# working.net
KiCad netlist of a schematic drawn in EAGLE
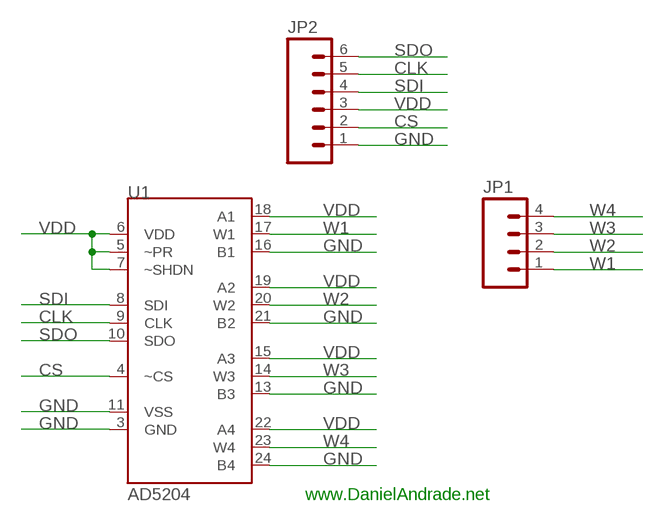
[diagram p0: schematic, sheet 1]

(export (version "E")
  (design (tool "Eeschema 10.0.6"))
  (components
    (comp (ref "JP1")
      (value "M04PTH")
      (footprint "eagle-import:1X04")
      (libsource (lib "eagle-import") (part "M04PTH"))
    )
    (comp (ref "JP2")
      (value "M06SIP")
      (footprint "eagle-import:1X06")
      (libsource (lib "eagle-import") (part "M06SIP"))
    )
    (comp (ref "U1")
      (value "AD5204")
      (footprint "eagle-import:SO24W")
      (libsource (lib "eagle-import") (part "AD5204"))
    )
  )
  (nets
    (net (code "1") (name "/CLK") (class "Default")
      (node (ref "JP2") (pin "5") (pinfunction "5_5") (pintype "passive"))
      (node (ref "U1") (pin "9") (pinfunction "CLK_9") (pintype "bidirectional"))
    )
    (net (code "2") (name "/CS") (class "Default")
      (node (ref "JP2") (pin "2") (pinfunction "2_2") (pintype "passive"))
      (node (ref "U1") (pin "4") (pinfunction "~{CS}_4") (pintype "bidirectional"))
    )
    (net (code "3") (name "/GND") (class "Default")
      (node (ref "JP2") (pin "1") (pinfunction "1_1") (pintype "passive"))
      (node (ref "U1") (pin "11") (pinfunction "VSS_11") (pintype "bidirectional"))
      (node (ref "U1") (pin "13") (pinfunction "B3_13") (pintype "bidirectional"))
      (node (ref "U1") (pin "16") (pinfunction "B1_16") (pintype "bidirectional"))
      (node (ref "U1") (pin "21") (pinfunction "B2_21") (pintype "bidirectional"))
      (node (ref "U1") (pin "24") (pinfunction "B4_24") (pintype "bidirectional"))
      (node (ref "U1") (pin "3") (pinfunction "GND_3") (pintype "bidirectional"))
    )
    (net (code "4") (name "/SDI") (class "Default")
      (node (ref "JP2") (pin "4") (pinfunction "4_4") (pintype "passive"))
      (node (ref "U1") (pin "8") (pinfunction "SDI_8") (pintype "bidirectional"))
    )
    (net (code "5") (name "/SDO") (class "Default")
      (node (ref "JP2") (pin "6") (pinfunction "6_6") (pintype "passive"))
      (node (ref "U1") (pin "10") (pinfunction "SDO_10") (pintype "bidirectional"))
    )
    (net (code "6") (name "/VDD") (class "Default")
      (node (ref "JP2") (pin "3") (pinfunction "3_3") (pintype "passive"))
      (node (ref "U1") (pin "15") (pinfunction "A3_15") (pintype "bidirectional"))
      (node (ref "U1") (pin "18") (pinfunction "A1_18") (pintype "bidirectional"))
      (node (ref "U1") (pin "19") (pinfunction "A2_19") (pintype "bidirectional"))
      (node (ref "U1") (pin "22") (pinfunction "A4_22") (pintype "bidirectional"))
      (node (ref "U1") (pin "5") (pinfunction "~{PR}_5") (pintype "bidirectional"))
      (node (ref "U1") (pin "6") (pinfunction "VDD_6") (pintype "bidirectional"))
      (node (ref "U1") (pin "7") (pinfunction "~{SHDN}_7") (pintype "bidirectional"))
    )
    (net (code "7") (name "/W1") (class "Default")
      (node (ref "JP1") (pin "1") (pinfunction "1_1") (pintype "passive"))
      (node (ref "U1") (pin "17") (pinfunction "W1_17") (pintype "bidirectional"))
    )
    (net (code "8") (name "/W2") (class "Default")
      (node (ref "JP1") (pin "2") (pinfunction "2_2") (pintype "passive"))
      (node (ref "U1") (pin "20") (pinfunction "W2_20") (pintype "bidirectional"))
    )
    (net (code "9") (name "/W3") (class "Default")
      (node (ref "JP1") (pin "3") (pinfunction "3_3") (pintype "passive"))
      (node (ref "U1") (pin "14") (pinfunction "W3_14") (pintype "bidirectional"))
    )
    (net (code "10") (name "/W4") (class "Default")
      (node (ref "JP1") (pin "4") (pinfunction "4_4") (pintype "passive"))
      (node (ref "U1") (pin "23") (pinfunction "W4_23") (pintype "bidirectional"))
    )
  )
)
